# F40_USB_HUB_2026-08-06.net
KiCad netlist of a schematic drawn in EasyEDA Pro
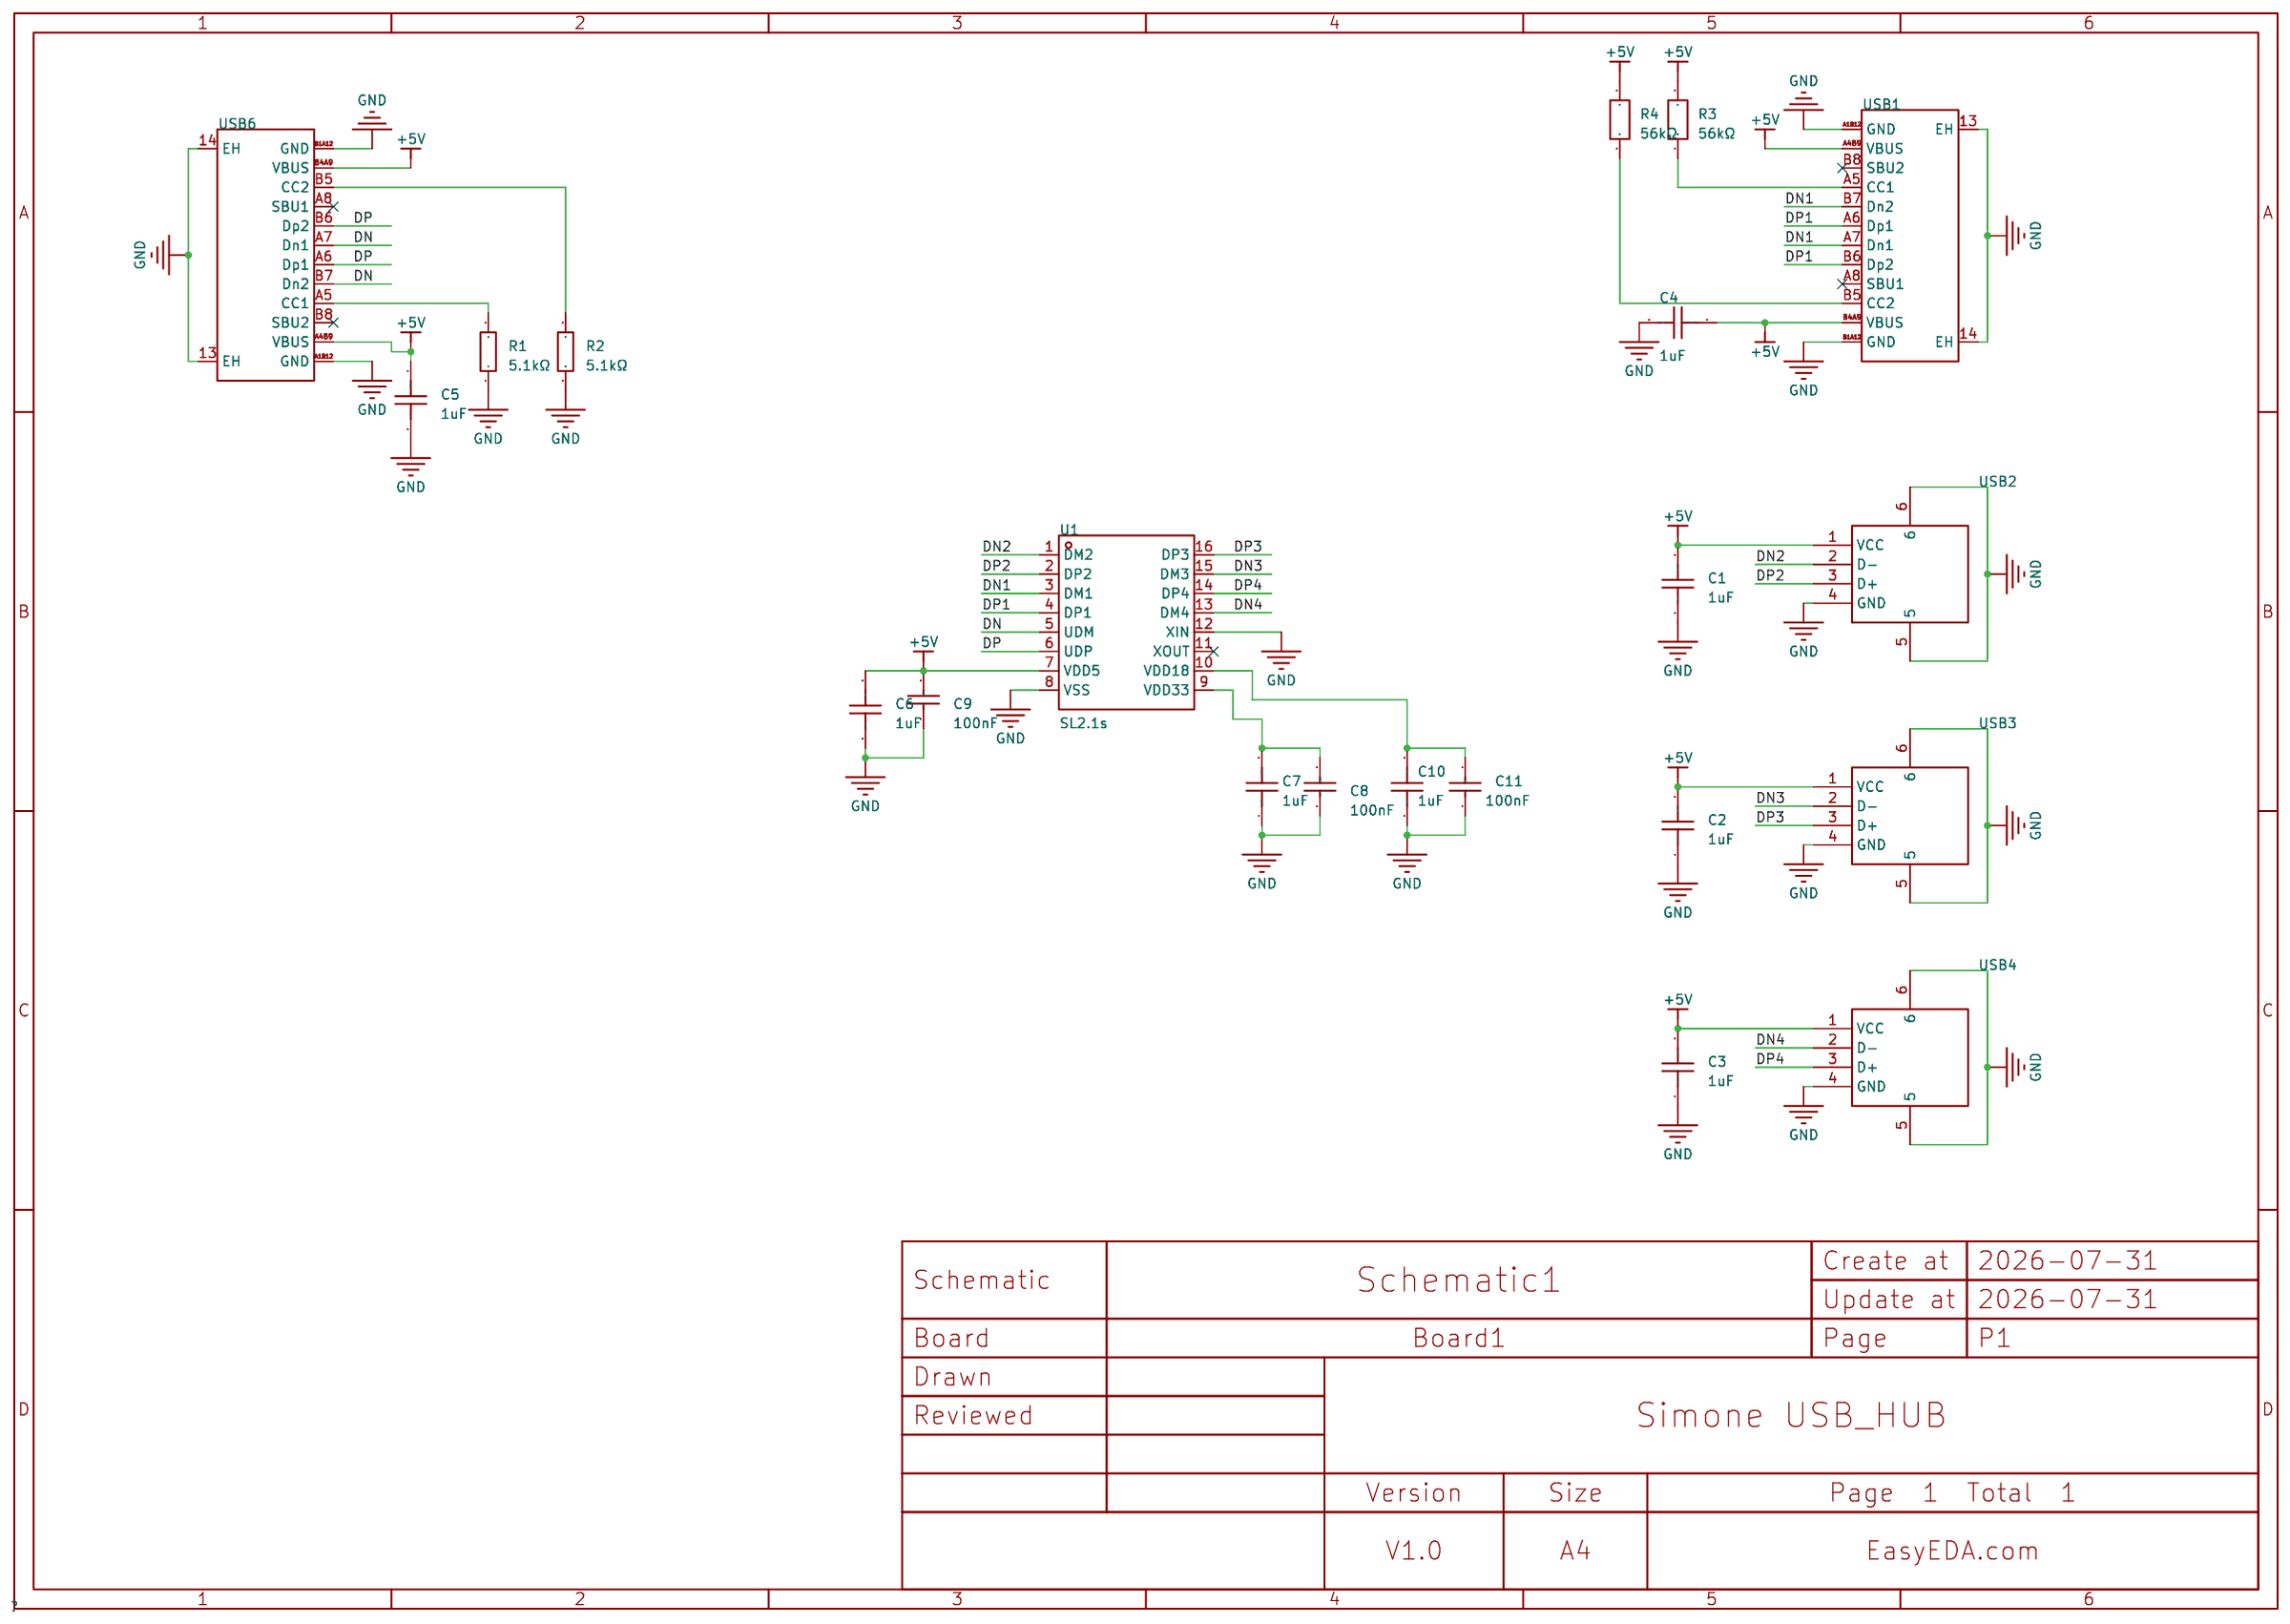
[diagram p0: schematic sheet]

(export (version "E")
  (design (tool "Eeschema 10.0.6"))
  (components
    (comp (ref "C1")
      (value "1uF")
      (footprint "easyedapro:C0603")
      (description "Capacitance:1uF Tolerance:±10% Tolerance:±10% Voltage Rating:50V Temperature Coefficient:X5R")
      (fields
        (field (name "Manufacturer Part") "CL10A105KB8NNNC")
        (field (name "Manufacturer") "SAMSUNG(三星)")
      )
      (libsource (lib "easyedapro") (part "CL10A105KB8NNNC"))
    )
    (comp (ref "C2")
      (value "1uF")
      (footprint "easyedapro:C0603")
      (description "Capacitance:1uF Tolerance:±10% Tolerance:±10% Voltage Rating:50V Temperature Coefficient:X5R")
      (fields
        (field (name "Manufacturer Part") "CL10A105KB8NNNC")
        (field (name "Manufacturer") "SAMSUNG(三星)")
      )
      (libsource (lib "easyedapro") (part "CL10A105KB8NNNC"))
    )
    (comp (ref "C3")
      (value "1uF")
      (footprint "easyedapro:C0603")
      (description "Capacitance:1uF Tolerance:±10% Tolerance:±10% Voltage Rating:50V Temperature Coefficient:X5R")
      (fields
        (field (name "Manufacturer Part") "CL10A105KB8NNNC")
        (field (name "Manufacturer") "SAMSUNG(三星)")
      )
      (libsource (lib "easyedapro") (part "CL10A105KB8NNNC"))
    )
    (comp (ref "C4")
      (value "1uF")
      (footprint "easyedapro:C0603")
      (description "Capacitance:1uF Tolerance:±10% Tolerance:±10% Voltage Rating:50V Temperature Coefficient:X5R")
      (fields
        (field (name "Manufacturer Part") "CL10A105KB8NNNC")
        (field (name "Manufacturer") "SAMSUNG(三星)")
      )
      (libsource (lib "easyedapro") (part "CL10A105KB8NNNC"))
    )
    (comp (ref "C5")
      (value "1uF")
      (footprint "easyedapro:C0603")
      (description "Capacitance:1uF Tolerance:±10% Tolerance:±10% Voltage Rating:50V Temperature Coefficient:X5R")
      (fields
        (field (name "Manufacturer Part") "CL10A105KB8NNNC")
        (field (name "Manufacturer") "SAMSUNG(三星)")
      )
      (libsource (lib "easyedapro") (part "CL10A105KB8NNNC"))
    )
    (comp (ref "C6")
      (value "1uF")
      (footprint "easyedapro:C0603")
      (description "Capacitance:1uF Tolerance:±10% Tolerance:±10% Voltage Rating:50V Temperature Coefficient:X5R")
      (fields
        (field (name "Manufacturer Part") "CL10A105KB8NNNC")
        (field (name "Manufacturer") "SAMSUNG(三星)")
      )
      (libsource (lib "easyedapro") (part "CL10A105KB8NNNC"))
    )
    (comp (ref "C7")
      (value "1uF")
      (footprint "easyedapro:C0603")
      (description "Capacitance:1uF Tolerance:±10% Tolerance:±10% Voltage Rating:50V Temperature Coefficient:X5R")
      (fields
        (field (name "Manufacturer Part") "CL10A105KB8NNNC")
        (field (name "Manufacturer") "SAMSUNG(三星)")
      )
      (libsource (lib "easyedapro") (part "CL10A105KB8NNNC"))
    )
    (comp (ref "C8")
      (value "100nF")
      (footprint "easyedapro:C0603")
      (fields
        (field (name "Manufacturer Part") "CC0603JRX7R9BB104")
        (field (name "Manufacturer") "YAGEO(国巨)")
        (field (name "Tolerance") "±5%")
      )
      (libsource (lib "easyedapro") (part "CC0603JRX7R9BB104"))
    )
    (comp (ref "C9")
      (value "100nF")
      (footprint "easyedapro:C0603")
      (fields
        (field (name "Manufacturer Part") "CC0603JRX7R9BB104")
        (field (name "Manufacturer") "YAGEO(国巨)")
        (field (name "Tolerance") "±5%")
      )
      (libsource (lib "easyedapro") (part "CC0603JRX7R9BB104"))
    )
    (comp (ref "C10")
      (value "1uF")
      (footprint "easyedapro:C0603")
      (description "Capacitance:1uF Tolerance:±10% Tolerance:±10% Voltage Rating:50V Temperature Coefficient:X5R")
      (fields
        (field (name "Manufacturer Part") "CL10A105KB8NNNC")
        (field (name "Manufacturer") "SAMSUNG(三星)")
      )
      (libsource (lib "easyedapro") (part "CL10A105KB8NNNC"))
    )
    (comp (ref "C11")
      (value "100nF")
      (footprint "easyedapro:C0603")
      (fields
        (field (name "Manufacturer Part") "CC0603JRX7R9BB104")
        (field (name "Manufacturer") "YAGEO(国巨)")
        (field (name "Tolerance") "±5%")
      )
      (libsource (lib "easyedapro") (part "CC0603JRX7R9BB104"))
    )
    (comp (ref "R1")
      (value "5.1kΩ")
      (footprint "easyedapro:R0603")
      (fields
        (field (name "Manufacturer Part") "0603WAF5101T5E")
        (field (name "Manufacturer") "UNI-ROYAL(厚声)")
        (field (name "Tolerance") "±1%")
      )
      (libsource (lib "easyedapro") (part "0603WAF5101T5E"))
    )
    (comp (ref "R2")
      (value "5.1kΩ")
      (footprint "easyedapro:R0603")
      (fields
        (field (name "Manufacturer Part") "0603WAF5101T5E")
        (field (name "Manufacturer") "UNI-ROYAL(厚声)")
        (field (name "Tolerance") "±1%")
      )
      (libsource (lib "easyedapro") (part "0603WAF5101T5E"))
    )
    (comp (ref "R3")
      (value "56kΩ")
      (footprint "easyedapro:R0603")
      (fields
        (field (name "Manufacturer Part") "SCR0603J56K")
        (field (name "Manufacturer") "VO(翔胜)")
        (field (name "Tolerance") "±5%")
      )
      (libsource (lib "easyedapro") (part "SCR0603J56K"))
    )
    (comp (ref "R4")
      (value "56kΩ")
      (footprint "easyedapro:R0603")
      (fields
        (field (name "Manufacturer Part") "SCR0603J56K")
        (field (name "Manufacturer") "VO(翔胜)")
        (field (name "Tolerance") "±5%")
      )
      (libsource (lib "easyedapro") (part "SCR0603J56K"))
    )
    (comp (ref "U1")
      (value "SL2.1s")
      (footprint "easyedapro:SSOP-16_L4.6-W2.6-P0.53-LS4.0-BL")
      (fields (field (name "Manufacturer") "CoreChips(和芯润德)"))
      (libsource (lib "easyedapro") (part "SL2.1S"))
    )
    (comp (ref "USB1")
      (value "TYPE-C 16PIN 2MD(073)")
      (footprint "easyedapro:USB-C-SMD_TYPE-C-16PIN-2MD-073")
      (fields (field (name "Manufacturer") "SHOU HAN(首韩)"))
      (libsource (lib "easyedapro") (part "TYPE-C 16PIN 2MD(073)"))
    )
    (comp (ref "USB2")
      (value "10.0 QHHTZB6.3")
      (footprint "easyedapro:USB-A-TH_10.0QHHTZB6.3")
      (fields (field (name "Manufacturer") "SHOU HAN(首韩)"))
      (libsource (lib "easyedapro") (part "10.0 QHHTZB6.3"))
    )
    (comp (ref "USB3")
      (value "10.0 QHHTZB6.3")
      (footprint "easyedapro:USB-A-TH_10.0QHHTZB6.3")
      (fields (field (name "Manufacturer") "SHOU HAN(首韩)"))
      (libsource (lib "easyedapro") (part "10.0 QHHTZB6.3"))
    )
    (comp (ref "USB4")
      (value "10.0 QHHTZB6.3")
      (footprint "easyedapro:USB-A-TH_10.0QHHTZB6.3")
      (fields (field (name "Manufacturer") "SHOU HAN(首韩)"))
      (libsource (lib "easyedapro") (part "10.0 QHHTZB6.3"))
    )
    (comp (ref "USB6")
      (value "TYPE-C 16PIN 2MD(073)")
      (footprint "easyedapro:USB-C-SMD_TYPE-C-16PIN-2MD-073")
      (fields (field (name "Manufacturer") "SHOU HAN(首韩)"))
      (libsource (lib "easyedapro") (part "TYPE-C 16PIN 2MD(073)"))
    )
  )
  (nets
    (net (code "1") (name "+5V") (class "Default")
      (node (ref "C1") (pin "2") (pinfunction "2_2") (pintype "unspecified"))
      (node (ref "C2") (pin "2") (pinfunction "2_2") (pintype "unspecified"))
      (node (ref "C3") (pin "2") (pinfunction "2_2") (pintype "unspecified"))
      (node (ref "C4") (pin "1") (pinfunction "1_1") (pintype "unspecified"))
      (node (ref "C5") (pin "1") (pinfunction "1_1") (pintype "unspecified"))
      (node (ref "C6") (pin "2") (pinfunction "2_2") (pintype "unspecified"))
      (node (ref "C9") (pin "2") (pinfunction "2_2") (pintype "input"))
      (node (ref "R3") (pin "2") (pinfunction "2_2") (pintype "unspecified"))
      (node (ref "R4") (pin "2") (pinfunction "2_2") (pintype "unspecified"))
      (node (ref "U1") (pin "7") (pinfunction "VDD5_7") (pintype "unspecified"))
      (node (ref "USB1") (pin "A4B9") (pinfunction "VBUS_A4B9") (pintype "unspecified"))
      (node (ref "USB1") (pin "B4A9") (pinfunction "VBUS_B4A9") (pintype "unspecified"))
      (node (ref "USB2") (pin "1") (pinfunction "VCC_1") (pintype "unspecified"))
      (node (ref "USB3") (pin "1") (pinfunction "VCC_1") (pintype "unspecified"))
      (node (ref "USB4") (pin "1") (pinfunction "VCC_1") (pintype "unspecified"))
      (node (ref "USB6") (pin "A4B9") (pinfunction "VBUS_A4B9") (pintype "unspecified"))
      (node (ref "USB6") (pin "B4A9") (pinfunction "VBUS_B4A9") (pintype "unspecified"))
    )
    (net (code "2") (name "/DN") (class "Default")
      (node (ref "U1") (pin "5") (pinfunction "UDM_5") (pintype "unspecified"))
      (node (ref "USB6") (pin "A7") (pinfunction "Dn1_A7") (pintype "unspecified"))
      (node (ref "USB6") (pin "B7") (pinfunction "Dn2_B7") (pintype "unspecified"))
    )
    (net (code "3") (name "/DN1") (class "Default")
      (node (ref "U1") (pin "3") (pinfunction "DM1_3") (pintype "unspecified"))
      (node (ref "USB1") (pin "A7") (pinfunction "Dn1_A7") (pintype "unspecified"))
      (node (ref "USB1") (pin "B7") (pinfunction "Dn2_B7") (pintype "unspecified"))
    )
    (net (code "4") (name "/DN2") (class "Default")
      (node (ref "U1") (pin "1") (pinfunction "DM2_1") (pintype "unspecified"))
      (node (ref "USB2") (pin "2") (pinfunction "D-_2") (pintype "unspecified"))
    )
    (net (code "5") (name "/DN3") (class "Default")
      (node (ref "U1") (pin "15") (pinfunction "DM3_15") (pintype "unspecified"))
      (node (ref "USB3") (pin "2") (pinfunction "D-_2") (pintype "unspecified"))
    )
    (net (code "6") (name "/DN4") (class "Default")
      (node (ref "U1") (pin "13") (pinfunction "DM4_13") (pintype "unspecified"))
      (node (ref "USB4") (pin "2") (pinfunction "D-_2") (pintype "unspecified"))
    )
    (net (code "7") (name "/DP") (class "Default")
      (node (ref "U1") (pin "6") (pinfunction "UDP_6") (pintype "unspecified"))
      (node (ref "USB6") (pin "A6") (pinfunction "Dp1_A6") (pintype "unspecified"))
      (node (ref "USB6") (pin "B6") (pinfunction "Dp2_B6") (pintype "unspecified"))
    )
    (net (code "8") (name "/DP1") (class "Default")
      (node (ref "U1") (pin "4") (pinfunction "DP1_4") (pintype "unspecified"))
      (node (ref "USB1") (pin "A6") (pinfunction "Dp1_A6") (pintype "unspecified"))
      (node (ref "USB1") (pin "B6") (pinfunction "Dp2_B6") (pintype "unspecified"))
    )
    (net (code "9") (name "/DP2") (class "Default")
      (node (ref "U1") (pin "2") (pinfunction "DP2_2") (pintype "unspecified"))
      (node (ref "USB2") (pin "3") (pinfunction "D+_3") (pintype "unspecified"))
    )
    (net (code "10") (name "/DP3") (class "Default")
      (node (ref "U1") (pin "16") (pinfunction "DP3_16") (pintype "unspecified"))
      (node (ref "USB3") (pin "3") (pinfunction "D+_3") (pintype "unspecified"))
    )
    (net (code "11") (name "/DP4") (class "Default")
      (node (ref "U1") (pin "14") (pinfunction "DP4_14") (pintype "unspecified"))
      (node (ref "USB4") (pin "3") (pinfunction "D+_3") (pintype "unspecified"))
    )
    (net (code "12") (name "GND") (class "Default")
      (node (ref "C1") (pin "1") (pinfunction "1_1") (pintype "unspecified"))
      (node (ref "C10") (pin "1") (pinfunction "1_1") (pintype "unspecified"))
      (node (ref "C11") (pin "1") (pinfunction "1_1") (pintype "input"))
      (node (ref "C2") (pin "1") (pinfunction "1_1") (pintype "unspecified"))
      (node (ref "C3") (pin "1") (pinfunction "1_1") (pintype "unspecified"))
      (node (ref "C4") (pin "2") (pinfunction "2_2") (pintype "unspecified"))
      (node (ref "C5") (pin "2") (pinfunction "2_2") (pintype "unspecified"))
      (node (ref "C6") (pin "1") (pinfunction "1_1") (pintype "unspecified"))
      (node (ref "C7") (pin "1") (pinfunction "1_1") (pintype "unspecified"))
      (node (ref "C8") (pin "1") (pinfunction "1_1") (pintype "input"))
      (node (ref "C9") (pin "1") (pinfunction "1_1") (pintype "input"))
      (node (ref "R1") (pin "1") (pinfunction "1_1") (pintype "input"))
      (node (ref "R2") (pin "2") (pinfunction "2_2") (pintype "input"))
      (node (ref "U1") (pin "12") (pinfunction "XIN_12") (pintype "unspecified"))
      (node (ref "U1") (pin "8") (pinfunction "VSS_8") (pintype "unspecified"))
      (node (ref "USB1") (pin "13") (pinfunction "EH_13") (pintype "unspecified"))
      (node (ref "USB1") (pin "14") (pinfunction "EH_14") (pintype "unspecified"))
      (node (ref "USB1") (pin "A1B12") (pinfunction "GND_A1B12") (pintype "unspecified"))
      (node (ref "USB1") (pin "B1A12") (pinfunction "GND_B1A12") (pintype "unspecified"))
      (node (ref "USB2") (pin "4") (pinfunction "GND_4") (pintype "unspecified"))
      (node (ref "USB2") (pin "5") (pinfunction "5_5") (pintype "unspecified"))
      (node (ref "USB2") (pin "6") (pinfunction "6_6") (pintype "unspecified"))
      (node (ref "USB3") (pin "4") (pinfunction "GND_4") (pintype "unspecified"))
      (node (ref "USB3") (pin "5") (pinfunction "5_5") (pintype "unspecified"))
      (node (ref "USB3") (pin "6") (pinfunction "6_6") (pintype "unspecified"))
      (node (ref "USB4") (pin "4") (pinfunction "GND_4") (pintype "unspecified"))
      (node (ref "USB4") (pin "5") (pinfunction "5_5") (pintype "unspecified"))
      (node (ref "USB4") (pin "6") (pinfunction "6_6") (pintype "unspecified"))
      (node (ref "USB6") (pin "13") (pinfunction "EH_13") (pintype "unspecified"))
      (node (ref "USB6") (pin "14") (pinfunction "EH_14") (pintype "unspecified"))
      (node (ref "USB6") (pin "A1B12") (pinfunction "GND_A1B12") (pintype "unspecified"))
      (node (ref "USB6") (pin "B1A12") (pinfunction "GND_B1A12") (pintype "unspecified"))
    )
    (net (code "13") (name "Net-(U1-VDD18)") (class "Default")
      (node (ref "C10") (pin "2") (pinfunction "2_2") (pintype "unspecified"))
      (node (ref "C11") (pin "2") (pinfunction "2_2") (pintype "input"))
      (node (ref "U1") (pin "10") (pinfunction "VDD18_10") (pintype "unspecified"))
    )
    (net (code "14") (name "Net-(U1-VDD33)") (class "Default")
      (node (ref "C7") (pin "2") (pinfunction "2_2") (pintype "unspecified"))
      (node (ref "C8") (pin "2") (pinfunction "2_2") (pintype "input"))
      (node (ref "U1") (pin "9") (pinfunction "VDD33_9") (pintype "unspecified"))
    )
    (net (code "15") (name "Net-(USB1-CC1)") (class "Default")
      (node (ref "R3") (pin "1") (pinfunction "1_1") (pintype "unspecified"))
      (node (ref "USB1") (pin "A5") (pinfunction "CC1_A5") (pintype "unspecified"))
    )
    (net (code "16") (name "Net-(USB1-CC2)") (class "Default")
      (node (ref "R4") (pin "1") (pinfunction "1_1") (pintype "unspecified"))
      (node (ref "USB1") (pin "B5") (pinfunction "CC2_B5") (pintype "unspecified"))
    )
    (net (code "17") (name "Net-(USB6-CC1)") (class "Default")
      (node (ref "R1") (pin "2") (pinfunction "2_2") (pintype "input"))
      (node (ref "USB6") (pin "A5") (pinfunction "CC1_A5") (pintype "unspecified"))
    )
    (net (code "18") (name "Net-(USB6-CC2)") (class "Default")
      (node (ref "R2") (pin "1") (pinfunction "1_1") (pintype "input"))
      (node (ref "USB6") (pin "B5") (pinfunction "CC2_B5") (pintype "unspecified"))
    )
    (net (code "19") (name "unconnected-(U1-XOUT-Pad11)") (class "Default")
      (node (ref "U1") (pin "11") (pinfunction "XOUT_11") (pintype "unspecified+no_connect"))
    )
    (net (code "20") (name "unconnected-(USB1-SBU1-PadA8)") (class "Default")
      (node (ref "USB1") (pin "A8") (pinfunction "SBU1_A8") (pintype "unspecified+no_connect"))
    )
    (net (code "21") (name "unconnected-(USB1-SBU2-PadB8)") (class "Default")
      (node (ref "USB1") (pin "B8") (pinfunction "SBU2_B8") (pintype "unspecified+no_connect"))
    )
    (net (code "22") (name "unconnected-(USB6-SBU1-PadA8)") (class "Default")
      (node (ref "USB6") (pin "A8") (pinfunction "SBU1_A8") (pintype "unspecified+no_connect"))
    )
    (net (code "23") (name "unconnected-(USB6-SBU2-PadB8)") (class "Default")
      (node (ref "USB6") (pin "B8") (pinfunction "SBU2_B8") (pintype "unspecified+no_connect"))
    )
  )
)
